# TRV_ANAREN.net
KiCad netlist of a schematic drawn in EAGLE
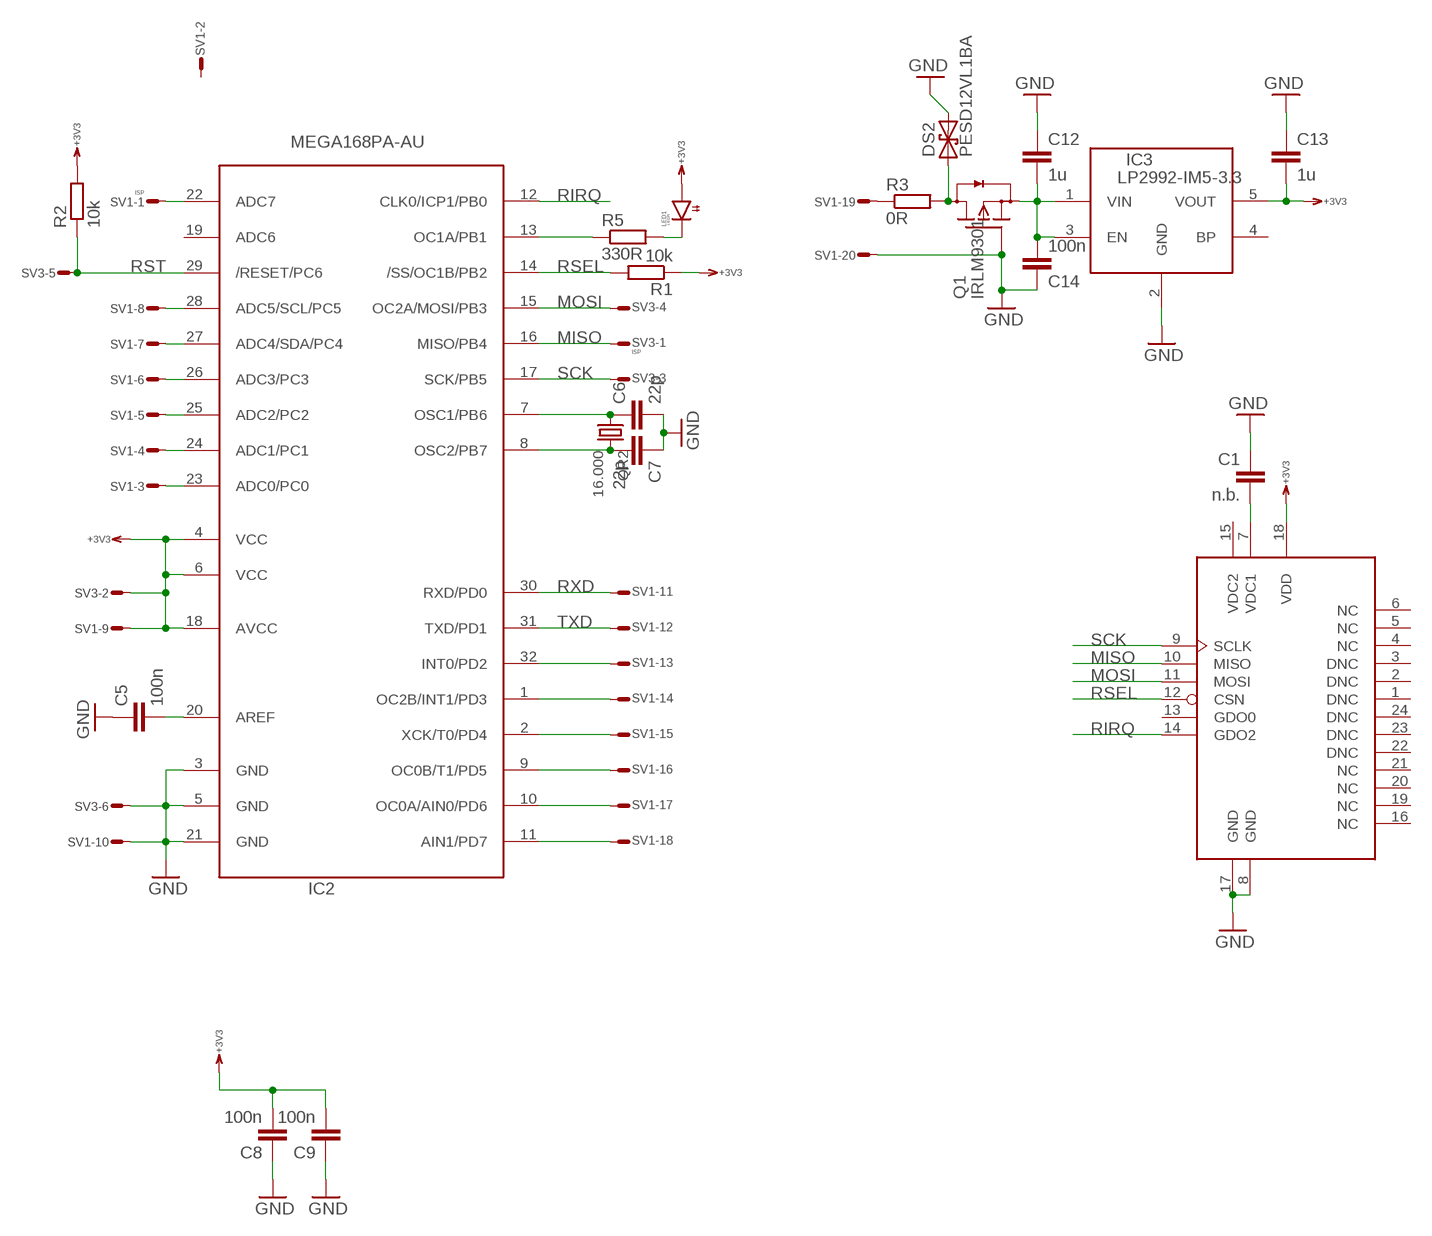
[diagram p0: schematic, sheet 1]

(export (version "E")
  (design (tool "Eeschema 10.0.6"))
  (components
    (comp (ref "C1")
      (value "n.b.")
      (footprint "eagle-import:0603")
      (libsource (lib "eagle-import") (part "C0603"))
    )
    (comp (ref "C5")
      (value "100n")
      (footprint "eagle-import:0603")
      (libsource (lib "eagle-import") (part "C0603"))
    )
    (comp (ref "C6")
      (value "22p")
      (footprint "eagle-import:0603")
      (libsource (lib "eagle-import") (part "C0603"))
    )
    (comp (ref "C7")
      (value "22p")
      (footprint "eagle-import:0603")
      (libsource (lib "eagle-import") (part "C0603"))
    )
    (comp (ref "C8")
      (value "100n")
      (footprint "eagle-import:0603")
      (libsource (lib "eagle-import") (part "C0603"))
    )
    (comp (ref "C9")
      (value "100n")
      (footprint "eagle-import:0603")
      (libsource (lib "eagle-import") (part "C0603"))
    )
    (comp (ref "C12")
      (value "1u")
      (footprint "eagle-import:0603")
      (libsource (lib "eagle-import") (part "C0603"))
    )
    (comp (ref "C13")
      (value "1u")
      (footprint "eagle-import:0603")
      (libsource (lib "eagle-import") (part "C0603"))
    )
    (comp (ref "C14")
      (value "100n")
      (footprint "eagle-import:0603")
      (libsource (lib "eagle-import") (part "C0603"))
    )
    (comp (ref "DS2")
      (value "PESD12VL1BA")
      (footprint "eagle-import:SOD323")
      (libsource (lib "eagle-import") (part "TVS-U323"))
    )
    (comp (ref "IC2")
      (value "MEGA168PA-AU")
      (footprint "eagle-import:TQFP32-08")
      (libsource (lib "eagle-import") (part "MEGA168PA"))
    )
    (comp (ref "IC3")
      (value "LP2992-IM5-3.3")
      (footprint "eagle-import:SOT23-5")
      (libsource (lib "eagle-import") (part "LDO"))
    )
    (comp (ref "LED1")
      (value "LEDR")
      (footprint "eagle-import:0603")
      (libsource (lib "eagle-import") (part "LED0603"))
    )
    (comp (ref "Q1")
      (value "IRLM9301")
      (footprint "eagle-import:SOT23")
      (libsource (lib "eagle-import") (part "FET-PDSOT23"))
    )
    (comp (ref "QR2")
      (value "16.000")
      (footprint "eagle-import:HC49U-V")
      (libsource (lib "eagle-import") (part "Q49UV"))
    )
    (comp (ref "R1")
      (value "10k")
      (footprint "eagle-import:0603")
      (libsource (lib "eagle-import") (part "R0603"))
    )
    (comp (ref "R2")
      (value "10k")
      (footprint "eagle-import:0603")
      (libsource (lib "eagle-import") (part "R0603"))
    )
    (comp (ref "R3")
      (value "0R")
      (footprint "eagle-import:0603")
      (libsource (lib "eagle-import") (part "R0603"))
    )
    (comp (ref "R5")
      (value "330R")
      (footprint "eagle-import:0603")
      (libsource (lib "eagle-import") (part "R0603"))
    )
    (comp (ref "RF1")
      (value "ANAREN")
      (footprint "eagle-import:ANAREN")
      (libsource (lib "eagle-import") (part "ANAREN"))
    )
    (comp (ref "SV1")
      (value "ISP")
      (footprint "eagle-import:ML20")
      (libsource (lib "eagle-import") (part "ML20?E"))
    )
    (comp (ref "SV3")
      (value "ISP")
      (footprint "eagle-import:ML6")
      (libsource (lib "eagle-import") (part "ML6E"))
    )
  )
  (nets
    (net (code "1") (name "+3V3") (class "Default")
      (node (ref "C13") (pin "2") (pinfunction "2_2") (pintype "passive"))
      (node (ref "C8") (pin "2") (pinfunction "2_2") (pintype "passive"))
      (node (ref "C9") (pin "2") (pinfunction "2_2") (pintype "passive"))
      (node (ref "IC2") (pin "18") (pinfunction "AVCC_18") (pintype "bidirectional"))
      (node (ref "IC2") (pin "4") (pinfunction "VCC_4") (pintype "bidirectional"))
      (node (ref "IC2") (pin "6") (pinfunction "VCC_6") (pintype "bidirectional"))
      (node (ref "IC3") (pin "5") (pinfunction "VOUT_5") (pintype "bidirectional"))
      (node (ref "LED1") (pin "1") (pinfunction "A_1") (pintype "bidirectional"))
      (node (ref "R1") (pin "1") (pinfunction "1_1") (pintype "passive"))
      (node (ref "R2") (pin "2") (pinfunction "2_2") (pintype "passive"))
      (node (ref "RF1") (pin "18") (pinfunction "VDD_18") (pintype "bidirectional"))
      (node (ref "SV1") (pin "9") (pinfunction "S_9") (pintype "passive"))
      (node (ref "SV3") (pin "2") (pinfunction "S_2") (pintype "passive"))
    )
    (net (code "2") (name "/MISO") (class "Default")
      (node (ref "IC2") (pin "16") (pinfunction "MISO/PB4_16") (pintype "bidirectional"))
      (node (ref "RF1") (pin "10") (pinfunction "MISO_10") (pintype "output"))
      (node (ref "SV3") (pin "1") (pinfunction "S_1") (pintype "passive"))
    )
    (net (code "3") (name "/MOSI") (class "Default")
      (node (ref "IC2") (pin "15") (pinfunction "OC2A/MOSI/PB3_15") (pintype "bidirectional"))
      (node (ref "RF1") (pin "11") (pinfunction "MOSI_11") (pintype "input"))
      (node (ref "SV3") (pin "4") (pinfunction "S_4") (pintype "passive"))
    )
    (net (code "4") (name "/RIRQ") (class "Default")
      (node (ref "IC2") (pin "12") (pinfunction "CLK0/ICP1/PB0_12") (pintype "bidirectional"))
      (node (ref "RF1") (pin "14") (pinfunction "GDO2_14") (pintype "bidirectional"))
    )
    (net (code "5") (name "/RSEL") (class "Default")
      (node (ref "IC2") (pin "14") (pinfunction "/SS/OC1B/PB2_14") (pintype "bidirectional"))
      (node (ref "R1") (pin "2") (pinfunction "2_2") (pintype "passive"))
      (node (ref "RF1") (pin "12") (pinfunction "CSN_12") (pintype "input"))
    )
    (net (code "6") (name "/RST") (class "Default")
      (node (ref "IC2") (pin "29") (pinfunction "/RESET/PC6_29") (pintype "bidirectional"))
      (node (ref "R2") (pin "1") (pinfunction "1_1") (pintype "passive"))
      (node (ref "SV3") (pin "5") (pinfunction "S_5") (pintype "passive"))
    )
    (net (code "7") (name "/RXD") (class "Default")
      (node (ref "IC2") (pin "30") (pinfunction "RXD/PD0_30") (pintype "bidirectional"))
      (node (ref "SV1") (pin "11") (pinfunction "S_11") (pintype "passive"))
    )
    (net (code "8") (name "/SCK") (class "Default")
      (node (ref "IC2") (pin "17") (pinfunction "SCK/PB5_17") (pintype "bidirectional"))
      (node (ref "RF1") (pin "9") (pinfunction "SCLK_9") (pintype "input"))
      (node (ref "SV3") (pin "3") (pinfunction "S_3") (pintype "passive"))
    )
    (net (code "9") (name "/TXD") (class "Default")
      (node (ref "IC2") (pin "31") (pinfunction "TXD/PD1_31") (pintype "bidirectional"))
      (node (ref "SV1") (pin "12") (pinfunction "S_12") (pintype "passive"))
    )
    (net (code "10") (name "GND") (class "Default")
      (node (ref "C1") (pin "1") (pinfunction "1_1") (pintype "passive"))
      (node (ref "C12") (pin "1") (pinfunction "1_1") (pintype "passive"))
      (node (ref "C13") (pin "1") (pinfunction "1_1") (pintype "passive"))
      (node (ref "C14") (pin "1") (pinfunction "1_1") (pintype "passive"))
      (node (ref "C5") (pin "1") (pinfunction "1_1") (pintype "passive"))
      (node (ref "C6") (pin "2") (pinfunction "2_2") (pintype "passive"))
      (node (ref "C7") (pin "1") (pinfunction "1_1") (pintype "passive"))
      (node (ref "C8") (pin "1") (pinfunction "1_1") (pintype "passive"))
      (node (ref "C9") (pin "1") (pinfunction "1_1") (pintype "passive"))
      (node (ref "DS2") (pin "C") (pinfunction "2_C") (pintype "passive"))
      (node (ref "IC2") (pin "21") (pinfunction "GND_21") (pintype "bidirectional"))
      (node (ref "IC2") (pin "3") (pinfunction "GND_3") (pintype "bidirectional"))
      (node (ref "IC2") (pin "5") (pinfunction "GND_5") (pintype "bidirectional"))
      (node (ref "IC3") (pin "2") (pinfunction "GND_2") (pintype "bidirectional"))
      (node (ref "Q1") (pin "1") (pinfunction "G_1") (pintype "passive"))
      (node (ref "RF1") (pin "17") (pinfunction "GND_17") (pintype "bidirectional"))
      (node (ref "RF1") (pin "8") (pinfunction "GND_8") (pintype "bidirectional"))
      (node (ref "SV1") (pin "10") (pinfunction "S_10") (pintype "passive"))
      (node (ref "SV1") (pin "20") (pinfunction "S_20") (pintype "passive"))
      (node (ref "SV3") (pin "6") (pinfunction "S_6") (pintype "passive"))
    )
    (net (code "11") (name "Net-(DS2-1)") (class "Default")
      (node (ref "DS2") (pin "A") (pinfunction "1_A") (pintype "passive"))
      (node (ref "Q1") (pin "3") (pinfunction "D_3") (pintype "passive"))
      (node (ref "R3") (pin "2") (pinfunction "2_2") (pintype "passive"))
    )
    (net (code "12") (name "Net-(IC2-ADC0{slash}PC0)") (class "Default")
      (node (ref "IC2") (pin "23") (pinfunction "ADC0/PC0_23") (pintype "bidirectional"))
      (node (ref "SV1") (pin "3") (pinfunction "S_3") (pintype "passive"))
    )
    (net (code "13") (name "Net-(IC2-ADC1{slash}PC1)") (class "Default")
      (node (ref "IC2") (pin "24") (pinfunction "ADC1/PC1_24") (pintype "bidirectional"))
      (node (ref "SV1") (pin "4") (pinfunction "S_4") (pintype "passive"))
    )
    (net (code "14") (name "Net-(IC2-ADC2{slash}PC2)") (class "Default")
      (node (ref "IC2") (pin "25") (pinfunction "ADC2/PC2_25") (pintype "bidirectional"))
      (node (ref "SV1") (pin "5") (pinfunction "S_5") (pintype "passive"))
    )
    (net (code "15") (name "Net-(IC2-ADC3{slash}PC3)") (class "Default")
      (node (ref "IC2") (pin "26") (pinfunction "ADC3/PC3_26") (pintype "bidirectional"))
      (node (ref "SV1") (pin "6") (pinfunction "S_6") (pintype "passive"))
    )
    (net (code "16") (name "Net-(IC2-ADC4{slash}SDA{slash}PC4)") (class "Default")
      (node (ref "IC2") (pin "27") (pinfunction "ADC4/SDA/PC4_27") (pintype "bidirectional"))
      (node (ref "SV1") (pin "7") (pinfunction "S_7") (pintype "passive"))
    )
    (net (code "17") (name "Net-(IC2-ADC5{slash}SCL{slash}PC5)") (class "Default")
      (node (ref "IC2") (pin "28") (pinfunction "ADC5/SCL/PC5_28") (pintype "bidirectional"))
      (node (ref "SV1") (pin "8") (pinfunction "S_8") (pintype "passive"))
    )
    (net (code "18") (name "Net-(IC2-ADC7)") (class "Default")
      (node (ref "IC2") (pin "22") (pinfunction "ADC7_22") (pintype "bidirectional"))
      (node (ref "SV1") (pin "1") (pinfunction "S_1") (pintype "passive"))
    )
    (net (code "19") (name "Net-(IC2-AIN1{slash}PD7)") (class "Default")
      (node (ref "IC2") (pin "11") (pinfunction "AIN1/PD7_11") (pintype "bidirectional"))
      (node (ref "SV1") (pin "18") (pinfunction "S_18") (pintype "passive"))
    )
    (net (code "20") (name "Net-(IC2-AREF)") (class "Default")
      (node (ref "C5") (pin "2") (pinfunction "2_2") (pintype "passive"))
      (node (ref "IC2") (pin "20") (pinfunction "AREF_20") (pintype "bidirectional"))
    )
    (net (code "21") (name "Net-(IC2-INT0{slash}PD2)") (class "Default")
      (node (ref "IC2") (pin "32") (pinfunction "INT0/PD2_32") (pintype "bidirectional"))
      (node (ref "SV1") (pin "13") (pinfunction "S_13") (pintype "passive"))
    )
    (net (code "22") (name "Net-(IC2-OC0A{slash}AIN0{slash}PD6)") (class "Default")
      (node (ref "IC2") (pin "10") (pinfunction "OC0A/AIN0/PD6_10") (pintype "bidirectional"))
      (node (ref "SV1") (pin "17") (pinfunction "S_17") (pintype "passive"))
    )
    (net (code "23") (name "Net-(IC2-OC0B{slash}T1{slash}PD5)") (class "Default")
      (node (ref "IC2") (pin "9") (pinfunction "OC0B/T1/PD5_9") (pintype "bidirectional"))
      (node (ref "SV1") (pin "16") (pinfunction "S_16") (pintype "passive"))
    )
    (net (code "24") (name "Net-(IC2-OC1A{slash}PB1)") (class "Default")
      (node (ref "IC2") (pin "13") (pinfunction "OC1A/PB1_13") (pintype "bidirectional"))
      (node (ref "R5") (pin "1") (pinfunction "1_1") (pintype "passive"))
    )
    (net (code "25") (name "Net-(IC2-OC2B{slash}INT1{slash}PD3)") (class "Default")
      (node (ref "IC2") (pin "1") (pinfunction "OC2B/INT1/PD3_1") (pintype "bidirectional"))
      (node (ref "SV1") (pin "14") (pinfunction "S_14") (pintype "passive"))
    )
    (net (code "26") (name "Net-(IC2-OSC1{slash}PB6)") (class "Default")
      (node (ref "C6") (pin "1") (pinfunction "1_1") (pintype "passive"))
      (node (ref "IC2") (pin "7") (pinfunction "OSC1/PB6_7") (pintype "bidirectional"))
      (node (ref "QR2") (pin "1") (pinfunction "1_1") (pintype "passive"))
    )
    (net (code "27") (name "Net-(IC2-OSC2{slash}PB7)") (class "Default")
      (node (ref "C7") (pin "2") (pinfunction "2_2") (pintype "passive"))
      (node (ref "IC2") (pin "8") (pinfunction "OSC2/PB7_8") (pintype "bidirectional"))
      (node (ref "QR2") (pin "2") (pinfunction "2_2") (pintype "passive"))
    )
    (net (code "28") (name "Net-(IC2-XCK{slash}T0{slash}PD4)") (class "Default")
      (node (ref "IC2") (pin "2") (pinfunction "XCK/T0/PD4_2") (pintype "bidirectional"))
      (node (ref "SV1") (pin "15") (pinfunction "S_15") (pintype "passive"))
    )
    (net (code "29") (name "Net-(IC3-EN)") (class "Default")
      (node (ref "C12") (pin "2") (pinfunction "2_2") (pintype "passive"))
      (node (ref "C14") (pin "2") (pinfunction "2_2") (pintype "passive"))
      (node (ref "IC3") (pin "1") (pinfunction "VIN_1") (pintype "bidirectional"))
      (node (ref "IC3") (pin "3") (pinfunction "EN_3") (pintype "bidirectional"))
      (node (ref "Q1") (pin "2") (pinfunction "S_2") (pintype "passive"))
    )
    (net (code "30") (name "Net-(LED1-C)") (class "Default")
      (node (ref "LED1") (pin "2") (pinfunction "C_2") (pintype "bidirectional"))
      (node (ref "R5") (pin "2") (pinfunction "2_2") (pintype "passive"))
    )
    (net (code "31") (name "Net-(RF1-VDC1)") (class "Default")
      (node (ref "C1") (pin "2") (pinfunction "2_2") (pintype "passive"))
      (node (ref "RF1") (pin "7") (pinfunction "VDC1_7") (pintype "bidirectional"))
    )
    (net (code "32") (name "Net-(SV1K-S)") (class "Default")
      (node (ref "R3") (pin "1") (pinfunction "1_1") (pintype "passive"))
      (node (ref "SV1") (pin "19") (pinfunction "S_19") (pintype "passive"))
    )
    (net (code "33") (name "unconnected-(IC2-ADC6-Pad19)") (class "Default")
      (node (ref "IC2") (pin "19") (pinfunction "ADC6_19") (pintype "bidirectional"))
    )
    (net (code "34") (name "unconnected-(IC3-BP-Pad4)") (class "Default")
      (node (ref "IC3") (pin "4") (pinfunction "BP_4") (pintype "bidirectional"))
    )
    (net (code "35") (name "unconnected-(RF1-DNC-Pad1)") (class "Default")
      (node (ref "RF1") (pin "1") (pinfunction "DNC_1") (pintype "bidirectional"))
    )
    (net (code "36") (name "unconnected-(RF1-DNC-Pad2)") (class "Default")
      (node (ref "RF1") (pin "2") (pinfunction "DNC_2") (pintype "bidirectional"))
    )
    (net (code "37") (name "unconnected-(RF1-DNC-Pad3)") (class "Default")
      (node (ref "RF1") (pin "3") (pinfunction "DNC_3") (pintype "bidirectional"))
    )
    (net (code "38") (name "unconnected-(RF1-DNC-Pad22)") (class "Default")
      (node (ref "RF1") (pin "22") (pinfunction "DNC_22") (pintype "bidirectional"))
    )
    (net (code "39") (name "unconnected-(RF1-DNC-Pad23)") (class "Default")
      (node (ref "RF1") (pin "23") (pinfunction "DNC_23") (pintype "bidirectional"))
    )
    (net (code "40") (name "unconnected-(RF1-DNC-Pad24)") (class "Default")
      (node (ref "RF1") (pin "24") (pinfunction "DNC_24") (pintype "bidirectional"))
    )
    (net (code "41") (name "unconnected-(RF1-GDO0-Pad13)") (class "Default")
      (node (ref "RF1") (pin "13") (pinfunction "GDO0_13") (pintype "bidirectional"))
    )
    (net (code "42") (name "unconnected-(RF1-NC-Pad4)") (class "Default")
      (node (ref "RF1") (pin "4") (pinfunction "NC_4") (pintype "bidirectional"))
    )
    (net (code "43") (name "unconnected-(RF1-NC-Pad5)") (class "Default")
      (node (ref "RF1") (pin "5") (pinfunction "NC_5") (pintype "bidirectional"))
    )
    (net (code "44") (name "unconnected-(RF1-NC-Pad6)") (class "Default")
      (node (ref "RF1") (pin "6") (pinfunction "NC_6") (pintype "bidirectional"))
    )
    (net (code "45") (name "unconnected-(RF1-NC-Pad16)") (class "Default")
      (node (ref "RF1") (pin "16") (pinfunction "NC_16") (pintype "bidirectional"))
    )
    (net (code "46") (name "unconnected-(RF1-NC-Pad19)") (class "Default")
      (node (ref "RF1") (pin "19") (pinfunction "NC_19") (pintype "bidirectional"))
    )
    (net (code "47") (name "unconnected-(RF1-NC-Pad20)") (class "Default")
      (node (ref "RF1") (pin "20") (pinfunction "NC_20") (pintype "bidirectional"))
    )
    (net (code "48") (name "unconnected-(RF1-NC-Pad21)") (class "Default")
      (node (ref "RF1") (pin "21") (pinfunction "NC_21") (pintype "bidirectional"))
    )
    (net (code "49") (name "unconnected-(RF1-VDC2-Pad15)") (class "Default")
      (node (ref "RF1") (pin "15") (pinfunction "VDC2_15") (pintype "bidirectional"))
    )
    (net (code "50") (name "unconnected-(SV1L-S-Pad2)") (class "Default")
      (node (ref "SV1") (pin "2") (pinfunction "S_2") (pintype "passive"))
    )
  )
)
